# drone_sch.net
KiCad netlist of a schematic drawn in Altium Designer
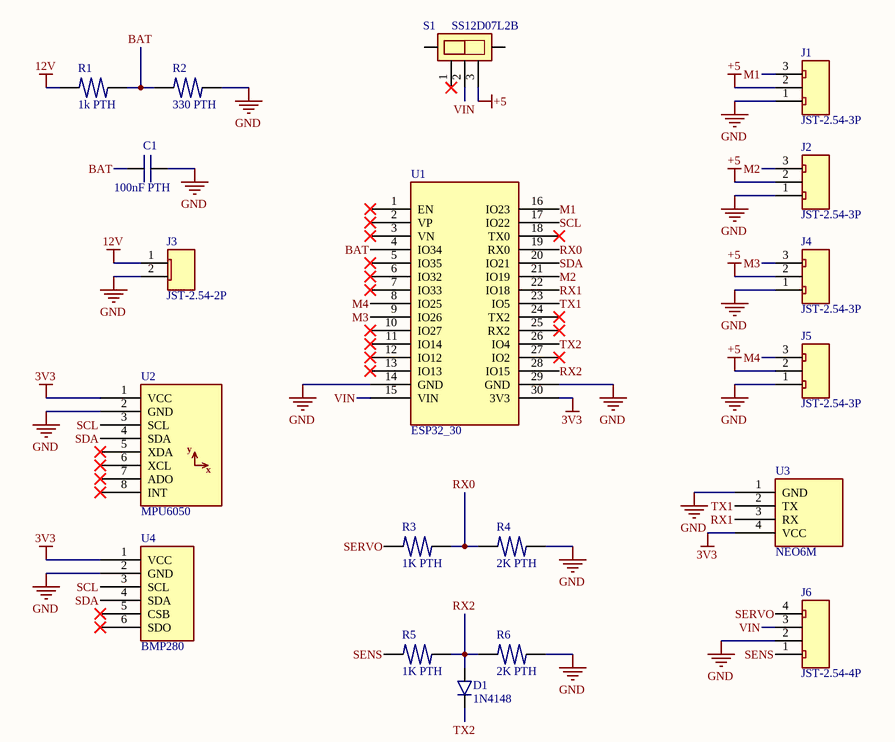
[diagram p0: drone_sch.SchDoc]

(export (version "E")
  (design (tool "Eeschema 10.0.6"))
  (components
    (comp (ref "C1")
      (value "100nF PTH")
      (footprint "CAPACITOR 103")
      (description "Ceramic Capacitor 103, 5mm.")
      (libsource (lib "Ceramic Capacitor") (part "CAPACITOR 103"))
    )
    (comp (ref "D1")
      (value "1N4148")
      (footprint "1N4148")
      (description "Diode Gen Purp 75V 300mA DO35")
      (libsource (lib "Diode") (part "1N4148"))
    )
    (comp (ref "J1")
      (value "JST-2.54-3P")
      (footprint "JST-2.54-3P")
      (description "Female Connector JST 3 Vias, 2.54mm.")
      (libsource (lib "Connectors") (part "JST-2.54-3P"))
    )
    (comp (ref "J2")
      (value "JST-2.54-3P")
      (footprint "JST-2.54-3P")
      (description "Female Connector JST 3 Vias, 2.54mm.")
      (libsource (lib "Connectors") (part "JST-2.54-3P"))
    )
    (comp (ref "J3")
      (value "JST-2.54-2P")
      (footprint "JST-2.54-2P")
      (description "Female Connector JST 2 Vias, 2.54mm.")
      (libsource (lib "Connectors") (part "JST-2.54-2P"))
    )
    (comp (ref "J4")
      (value "JST-2.54-3P")
      (footprint "JST-2.54-3P")
      (description "Female Connector JST 3 Vias, 2.54mm.")
      (libsource (lib "Connectors") (part "JST-2.54-3P"))
    )
    (comp (ref "J5")
      (value "JST-2.54-3P")
      (footprint "JST-2.54-3P")
      (description "Female Connector JST 3 Vias, 2.54mm.")
      (libsource (lib "Connectors") (part "JST-2.54-3P"))
    )
    (comp (ref "J6")
      (value "JST-2.54-4P")
      (footprint "JST-2.54-4P")
      (description "Female Connector JST 4 Vias, 2.54mm.")
      (libsource (lib "Connectors") (part "JST-2.54-4P"))
    )
    (comp (ref "R1")
      (value "1k PTH")
      (footprint "RESISTOR_PTH_9.5mm")
      (description "Generic Resistor 9.5mm.")
      (libsource (lib "Resistors") (part "RESISTOR_9.5mm"))
    )
    (comp (ref "R2")
      (value "330 PTH")
      (footprint "RESISTOR_PTH_9.5mm")
      (description "Generic Resistor 9.5mm.")
      (libsource (lib "Resistors") (part "RESISTOR_9.5mm"))
    )
    (comp (ref "R3")
      (value "1K PTH")
      (footprint "RESISTOR_PTH_9.5mm")
      (description "Generic Resistor 9.5mm.")
      (libsource (lib "Resistors") (part "RESISTOR_9.5mm"))
    )
    (comp (ref "R4")
      (value "2K PTH")
      (footprint "RESISTOR_PTH_9.5mm")
      (description "Generic Resistor 9.5mm.")
      (libsource (lib "Resistors") (part "RESISTOR_9.5mm"))
    )
    (comp (ref "R5")
      (value "1K PTH")
      (footprint "RESISTOR_PTH_9.5mm")
      (description "Generic Resistor 9.5mm.")
      (libsource (lib "Resistors") (part "RESISTOR_9.5mm"))
    )
    (comp (ref "R6")
      (value "2K PTH")
      (footprint "RESISTOR_PTH_9.5mm")
      (description "Generic Resistor 9.5mm.")
      (libsource (lib "Resistors") (part "RESISTOR_9.5mm"))
    )
    (comp (ref "S1")
      (value "SS12D07L2B")
      (footprint "SS12D07L2B")
      (description "Vertical Slide Switch 5 Pins 8.7x4.5x4.7mm.")
      (libsource (lib "Buttons & Switches") (part "SS12D07L2B"))
    )
    (comp (ref "U1")
      (value "ESP32_30")
      (footprint "ESP32_30")
      (description "Microcontoller Board 30 Pins Wifi 2.4GHz BLE 4.2 ESP32-WROOM-32D")
      (libsource (lib "Espressif Microcontrollers") (part "ESP32_30"))
    )
    (comp (ref "U2")
      (value "MPU6050")
      (footprint "MPU6050")
      (description "IMU ACCEL/GYRO 3-AXIS I2C")
      (libsource (lib "Sensors") (part "MPU6050"))
    )
    (comp (ref "U3") (value "NEO6M") (footprint "NEO6M") (libsource (lib "Sensors") (part "NEO6M")))
    (comp (ref "U4")
      (value "BMP280")
      (footprint "BMP280")
      (description "SENSOR ATMOSPHERIC PRESSURE/TEMPERATURE/ALTITUDE")
      (libsource (lib "Sensors") (part "BMP280"))
    )
  )
  (nets
    (net (code "1") (name "+5") (class "Default")
      (node (ref "J1") (pin "2") (pintype "passive"))
      (node (ref "J2") (pin "2") (pintype "passive"))
      (node (ref "J4") (pin "2") (pintype "passive"))
      (node (ref "J5") (pin "2") (pintype "passive"))
      (node (ref "S1") (pin "3") (pinfunction "3_3") (pintype "passive"))
    )
    (net (code "2") (name "/BAT") (class "Default")
      (node (ref "C1") (pin "2") (pinfunction "2_2") (pintype "passive"))
      (node (ref "R1") (pin "2") (pinfunction "2_2") (pintype "passive"))
      (node (ref "R2") (pin "1") (pinfunction "1_1") (pintype "passive"))
      (node (ref "U1") (pin "4") (pinfunction "IO34_4") (pintype "passive"))
    )
    (net (code "3") (name "/M1") (class "Default")
      (node (ref "J1") (pin "3") (pintype "passive"))
      (node (ref "U1") (pin "16") (pinfunction "IO23_16") (pintype "passive"))
    )
    (net (code "4") (name "/M2") (class "Default")
      (node (ref "J2") (pin "3") (pintype "passive"))
      (node (ref "U1") (pin "21") (pinfunction "IO19_21") (pintype "passive"))
    )
    (net (code "5") (name "/M3") (class "Default")
      (node (ref "J4") (pin "3") (pintype "passive"))
      (node (ref "U1") (pin "9") (pinfunction "IO26_9") (pintype "passive"))
    )
    (net (code "6") (name "/M4") (class "Default")
      (node (ref "J5") (pin "3") (pintype "passive"))
      (node (ref "U1") (pin "8") (pinfunction "IO25_8") (pintype "passive"))
    )
    (net (code "7") (name "/RX0") (class "Default")
      (node (ref "R3") (pin "2") (pinfunction "2_2") (pintype "passive"))
      (node (ref "R4") (pin "1") (pinfunction "1_1") (pintype "passive"))
      (node (ref "U1") (pin "19") (pinfunction "RX0_19") (pintype "passive"))
    )
    (net (code "8") (name "/RX1") (class "Default")
      (node (ref "U1") (pin "22") (pinfunction "IO18_22") (pintype "passive"))
      (node (ref "U3") (pin "3") (pinfunction "RX_3") (pintype "passive"))
    )
    (net (code "9") (name "/RX2") (class "Default")
      (node (ref "D1") (pin "1") (pinfunction "1_1") (pintype "passive"))
      (node (ref "R5") (pin "2") (pinfunction "2_2") (pintype "passive"))
      (node (ref "R6") (pin "1") (pinfunction "1_1") (pintype "passive"))
      (node (ref "U1") (pin "28") (pinfunction "IO15_28") (pintype "passive"))
    )
    (net (code "10") (name "/SCL") (class "Default")
      (node (ref "U1") (pin "17") (pinfunction "IO22_17") (pintype "passive"))
      (node (ref "U2") (pin "3") (pinfunction "SCL_3") (pintype "passive"))
      (node (ref "U4") (pin "3") (pinfunction "SCL_3") (pintype "passive"))
    )
    (net (code "11") (name "/SDA") (class "Default")
      (node (ref "U1") (pin "20") (pinfunction "IO21_20") (pintype "passive"))
      (node (ref "U2") (pin "4") (pinfunction "SDA_4") (pintype "passive"))
      (node (ref "U4") (pin "4") (pinfunction "SDA_4") (pintype "passive"))
    )
    (net (code "12") (name "/SENS") (class "Default")
      (node (ref "J6") (pin "1") (pintype "passive"))
      (node (ref "R5") (pin "1") (pinfunction "1_1") (pintype "passive"))
    )
    (net (code "13") (name "/SERVO") (class "Default")
      (node (ref "J6") (pin "4") (pintype "passive"))
      (node (ref "R3") (pin "1") (pinfunction "1_1") (pintype "passive"))
    )
    (net (code "14") (name "/TX1") (class "Default")
      (node (ref "U1") (pin "23") (pinfunction "IO5_23") (pintype "passive"))
      (node (ref "U3") (pin "2") (pinfunction "TX_2") (pintype "passive"))
    )
    (net (code "15") (name "/TX2") (class "Default")
      (node (ref "D1") (pin "2") (pintype "passive"))
      (node (ref "U1") (pin "26") (pinfunction "IO4_26") (pintype "passive"))
    )
    (net (code "16") (name "/VIN") (class "Default")
      (node (ref "J6") (pin "3") (pintype "passive"))
      (node (ref "S1") (pin "2") (pinfunction "2_2") (pintype "passive"))
      (node (ref "U1") (pin "15") (pinfunction "VIN_15") (pintype "passive"))
    )
    (net (code "17") (name "3V3") (class "Default")
      (node (ref "U1") (pin "30") (pinfunction "3V3_30") (pintype "passive"))
      (node (ref "U2") (pin "1") (pinfunction "VCC_1") (pintype "passive"))
      (node (ref "U3") (pin "4") (pinfunction "VCC_4") (pintype "passive"))
      (node (ref "U4") (pin "1") (pinfunction "VCC_1") (pintype "passive"))
    )
    (net (code "18") (name "12V") (class "Default")
      (node (ref "J3") (pin "1") (pintype "passive"))
      (node (ref "R1") (pin "1") (pinfunction "1_1") (pintype "passive"))
    )
    (net (code "19") (name "GND") (class "Default")
      (node (ref "C1") (pin "1") (pinfunction "1_1") (pintype "passive"))
      (node (ref "J1") (pin "1") (pintype "passive"))
      (node (ref "J2") (pin "1") (pintype "passive"))
      (node (ref "J3") (pin "2") (pintype "passive"))
      (node (ref "J4") (pin "1") (pintype "passive"))
      (node (ref "J5") (pin "1") (pintype "passive"))
      (node (ref "J6") (pin "2") (pintype "passive"))
      (node (ref "R2") (pin "2") (pinfunction "2_2") (pintype "passive"))
      (node (ref "R4") (pin "2") (pinfunction "2_2") (pintype "passive"))
      (node (ref "R6") (pin "2") (pinfunction "2_2") (pintype "passive"))
      (node (ref "U1") (pin "14") (pinfunction "GND_14") (pintype "passive"))
      (node (ref "U1") (pin "29") (pinfunction "GND_29") (pintype "passive"))
      (node (ref "U2") (pin "2") (pinfunction "GND_2") (pintype "passive"))
      (node (ref "U3") (pin "1") (pinfunction "GND_1") (pintype "passive"))
      (node (ref "U4") (pin "2") (pinfunction "GND_2") (pintype "passive"))
    )
    (net (code "20") (name "unconnected-(S1-Pad1)") (class "Default")
      (node (ref "S1") (pin "1") (pinfunction "1_1") (pintype "passive+no_connect"))
    )
    (net (code "21") (name "unconnected-(U1-EN-Pad1)") (class "Default")
      (node (ref "U1") (pin "1") (pinfunction "EN_1") (pintype "passive+no_connect"))
    )
    (net (code "22") (name "unconnected-(U1-IO2-Pad27)") (class "Default")
      (node (ref "U1") (pin "27") (pinfunction "IO2_27") (pintype "passive+no_connect"))
    )
    (net (code "23") (name "unconnected-(U1-IO12-Pad12)") (class "Default")
      (node (ref "U1") (pin "12") (pinfunction "IO12_12") (pintype "passive+no_connect"))
    )
    (net (code "24") (name "unconnected-(U1-IO13-Pad13)") (class "Default")
      (node (ref "U1") (pin "13") (pinfunction "IO13_13") (pintype "passive+no_connect"))
    )
    (net (code "25") (name "unconnected-(U1-IO14-Pad11)") (class "Default")
      (node (ref "U1") (pin "11") (pinfunction "IO14_11") (pintype "passive+no_connect"))
    )
    (net (code "26") (name "unconnected-(U1-IO27-Pad10)") (class "Default")
      (node (ref "U1") (pin "10") (pinfunction "IO27_10") (pintype "passive+no_connect"))
    )
    (net (code "27") (name "unconnected-(U1-IO32-Pad6)") (class "Default")
      (node (ref "U1") (pin "6") (pinfunction "IO32_6") (pintype "passive+no_connect"))
    )
    (net (code "28") (name "unconnected-(U1-IO33-Pad7)") (class "Default")
      (node (ref "U1") (pin "7") (pinfunction "IO33_7") (pintype "passive+no_connect"))
    )
    (net (code "29") (name "unconnected-(U1-IO35-Pad5)") (class "Default")
      (node (ref "U1") (pin "5") (pinfunction "IO35_5") (pintype "passive+no_connect"))
    )
    (net (code "30") (name "unconnected-(U1-RX2-Pad25)") (class "Default")
      (node (ref "U1") (pin "25") (pinfunction "RX2_25") (pintype "passive+no_connect"))
    )
    (net (code "31") (name "unconnected-(U1-TX0-Pad18)") (class "Default")
      (node (ref "U1") (pin "18") (pinfunction "TX0_18") (pintype "passive+no_connect"))
    )
    (net (code "32") (name "unconnected-(U1-TX2-Pad24)") (class "Default")
      (node (ref "U1") (pin "24") (pinfunction "TX2_24") (pintype "passive+no_connect"))
    )
    (net (code "33") (name "unconnected-(U1-VN-Pad3)") (class "Default")
      (node (ref "U1") (pin "3") (pinfunction "VN_3") (pintype "passive+no_connect"))
    )
    (net (code "34") (name "unconnected-(U1-VP-Pad2)") (class "Default")
      (node (ref "U1") (pin "2") (pinfunction "VP_2") (pintype "passive+no_connect"))
    )
    (net (code "35") (name "unconnected-(U2-ADO-Pad7)") (class "Default")
      (node (ref "U2") (pin "7") (pinfunction "ADO_7") (pintype "passive+no_connect"))
    )
    (net (code "36") (name "unconnected-(U2-INT-Pad8)") (class "Default")
      (node (ref "U2") (pin "8") (pinfunction "INT_8") (pintype "passive+no_connect"))
    )
    (net (code "37") (name "unconnected-(U2-XCL-Pad6)") (class "Default")
      (node (ref "U2") (pin "6") (pinfunction "XCL_6") (pintype "passive+no_connect"))
    )
    (net (code "38") (name "unconnected-(U2-XDA-Pad5)") (class "Default")
      (node (ref "U2") (pin "5") (pinfunction "XDA_5") (pintype "passive+no_connect"))
    )
    (net (code "39") (name "unconnected-(U4-CSB-Pad5)") (class "Default")
      (node (ref "U4") (pin "5") (pinfunction "CSB_5") (pintype "passive+no_connect"))
    )
    (net (code "40") (name "unconnected-(U4-SDO-Pad6)") (class "Default")
      (node (ref "U4") (pin "6") (pinfunction "SDO_6") (pintype "passive+no_connect"))
    )
  )
)
